# Toplevel.net
KiCad netlist of a schematic drawn in Altium Designer
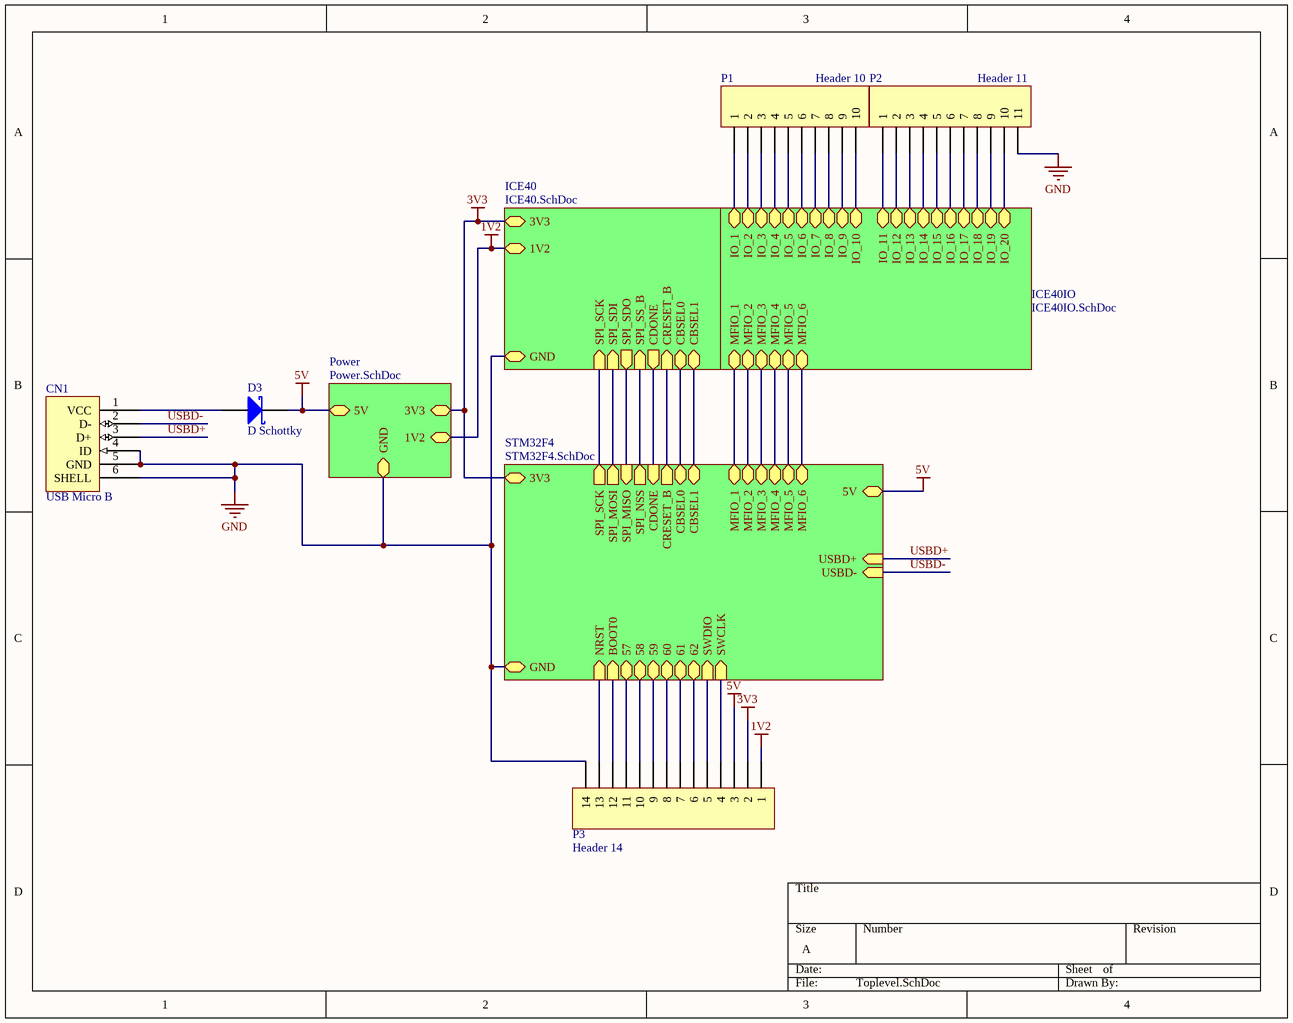
[diagram p0: Toplevel.SchDoc]

(export (version "E")
  (design (tool "Eeschema 10.0.6"))
  (components
    (comp (ref "CN1") (value "USB Micro B") (libsource (lib "PSV2") (part "USB Micro B")))
    (comp (ref "D3")
      (value "D Schottky")
      (footprint "SMB")
      (description "Schottky Diode")
      (fields (field (name "PUBLISHER") "Altium Limited"))
      (libsource (lib "Miscellaneous Devices") (part "D Schottky"))
    )
    (comp (ref "P1")
      (value "Header 10")
      (footprint "HDR1X10")
      (description "Header, 10-Pin")
      (fields (field (name "PUBLISHER") "Altium Limited"))
      (libsource (lib "Miscellaneous Connectors") (part "Header 10"))
    )
    (comp (ref "P2")
      (value "Header 11")
      (footprint "HDR1X11")
      (description "Header, 11-Pin")
      (fields (field (name "PUBLISHER") "Altium Limited"))
      (libsource (lib "Miscellaneous Connectors") (part "Header 11"))
    )
    (comp (ref "P3")
      (value "Header 14")
      (footprint "HDR1X14")
      (description "Header, 14-Pin")
      (fields (field (name "PUBLISHER") "Altium Limited"))
      (libsource (lib "Miscellaneous Connectors") (part "Header 14"))
    )
  )
  (nets
    (net (code "1") (name "/57") (class "Default")
      (node (ref "P3") (pin "11") (pinfunction "11_11") (pintype "passive"))
    )
    (net (code "2") (name "/58") (class "Default")
      (node (ref "P3") (pin "10") (pinfunction "10_10") (pintype "passive"))
    )
    (net (code "3") (name "/59") (class "Default")
      (node (ref "P3") (pin "9") (pinfunction "9_9") (pintype "passive"))
    )
    (net (code "4") (name "/60") (class "Default")
      (node (ref "P3") (pin "8") (pinfunction "8_8") (pintype "passive"))
    )
    (net (code "5") (name "/61") (class "Default")
      (node (ref "P3") (pin "7") (pinfunction "7_7") (pintype "passive"))
    )
    (net (code "6") (name "/62") (class "Default")
      (node (ref "P3") (pin "6") (pinfunction "6_6") (pintype "passive"))
    )
    (net (code "7") (name "/BOOT0") (class "Default")
      (node (ref "P3") (pin "12") (pinfunction "12_12") (pintype "passive"))
    )
    (net (code "12") (name "/IO_1") (class "Default")
      (node (ref "P1") (pin "1") (pinfunction "1_1") (pintype "passive"))
    )
    (net (code "13") (name "/IO_2") (class "Default")
      (node (ref "P1") (pin "2") (pinfunction "2_2") (pintype "passive"))
    )
    (net (code "14") (name "/IO_3") (class "Default")
      (node (ref "P1") (pin "3") (pinfunction "3_3") (pintype "passive"))
    )
    (net (code "15") (name "/IO_4") (class "Default")
      (node (ref "P1") (pin "4") (pinfunction "4_4") (pintype "passive"))
    )
    (net (code "16") (name "/IO_5") (class "Default")
      (node (ref "P1") (pin "5") (pinfunction "5_5") (pintype "passive"))
    )
    (net (code "17") (name "/IO_6") (class "Default")
      (node (ref "P1") (pin "6") (pinfunction "6_6") (pintype "passive"))
    )
    (net (code "18") (name "/IO_7") (class "Default")
      (node (ref "P1") (pin "7") (pinfunction "7_7") (pintype "passive"))
    )
    (net (code "19") (name "/IO_8") (class "Default")
      (node (ref "P1") (pin "8") (pinfunction "8_8") (pintype "passive"))
    )
    (net (code "20") (name "/IO_9") (class "Default")
      (node (ref "P1") (pin "9") (pinfunction "9_9") (pintype "passive"))
    )
    (net (code "21") (name "/IO_10") (class "Default")
      (node (ref "P1") (pin "10") (pinfunction "10_10") (pintype "passive"))
    )
    (net (code "22") (name "/IO_11") (class "Default")
      (node (ref "P2") (pin "1") (pinfunction "1_1") (pintype "passive"))
    )
    (net (code "23") (name "/IO_12") (class "Default")
      (node (ref "P2") (pin "2") (pinfunction "2_2") (pintype "passive"))
    )
    (net (code "24") (name "/IO_13") (class "Default")
      (node (ref "P2") (pin "3") (pinfunction "3_3") (pintype "passive"))
    )
    (net (code "25") (name "/IO_14") (class "Default")
      (node (ref "P2") (pin "4") (pinfunction "4_4") (pintype "passive"))
    )
    (net (code "26") (name "/IO_15") (class "Default")
      (node (ref "P2") (pin "5") (pinfunction "5_5") (pintype "passive"))
    )
    (net (code "27") (name "/IO_16") (class "Default")
      (node (ref "P2") (pin "6") (pinfunction "6_6") (pintype "passive"))
    )
    (net (code "28") (name "/IO_17") (class "Default")
      (node (ref "P2") (pin "7") (pinfunction "7_7") (pintype "passive"))
    )
    (net (code "29") (name "/IO_18") (class "Default")
      (node (ref "P2") (pin "8") (pinfunction "8_8") (pintype "passive"))
    )
    (net (code "30") (name "/IO_19") (class "Default")
      (node (ref "P2") (pin "9") (pinfunction "9_9") (pintype "passive"))
    )
    (net (code "31") (name "/IO_20") (class "Default")
      (node (ref "P2") (pin "10") (pinfunction "10_10") (pintype "passive"))
    )
    (net (code "38") (name "/NRST") (class "Default")
      (node (ref "P3") (pin "13") (pinfunction "13_13") (pintype "passive"))
    )
    (net (code "43") (name "/SWCLK") (class "Default")
      (node (ref "P3") (pin "4") (pinfunction "4_4") (pintype "passive"))
    )
    (net (code "44") (name "/SWDIO") (class "Default")
      (node (ref "P3") (pin "5") (pinfunction "5_5") (pintype "passive"))
    )
    (net (code "45") (name "/USBD+") (class "Default")
      (node (ref "CN1") (pin "3") (pinfunction "D+_3") (pintype "bidirectional"))
    )
    (net (code "46") (name "/USBD-") (class "Default")
      (node (ref "CN1") (pin "2") (pinfunction "D-_2") (pintype "bidirectional"))
    )
    (net (code "47") (name "1V2") (class "Default")
      (node (ref "P3") (pin "1") (pinfunction "1_1") (pintype "passive"))
    )
    (net (code "48") (name "3V3") (class "Default")
      (node (ref "P3") (pin "2") (pinfunction "2_2") (pintype "passive"))
    )
    (net (code "49") (name "5V") (class "Default")
      (node (ref "D3") (pin "2") (pinfunction "K_2") (pintype "passive"))
      (node (ref "P3") (pin "3") (pinfunction "3_3") (pintype "passive"))
    )
    (net (code "50") (name "GND") (class "Default")
      (node (ref "CN1") (pin "4") (pinfunction "ID_4") (pintype "input"))
      (node (ref "CN1") (pin "5") (pinfunction "GND_5") (pintype "power_in"))
      (node (ref "CN1") (pin "6") (pinfunction "SHELL_6") (pintype "power_in"))
      (node (ref "P2") (pin "11") (pinfunction "11_11") (pintype "passive"))
      (node (ref "P3") (pin "14") (pinfunction "14_14") (pintype "passive"))
    )
    (net (code "51") (name "Net-(CN1-VCC)") (class "Default")
      (node (ref "CN1") (pin "1") (pinfunction "VCC_1") (pintype "power_in"))
      (node (ref "D3") (pin "1") (pinfunction "A_1") (pintype "passive"))
    )
  )
)
